# shield_v3.net
KiCad netlist of a schematic drawn in EAGLE
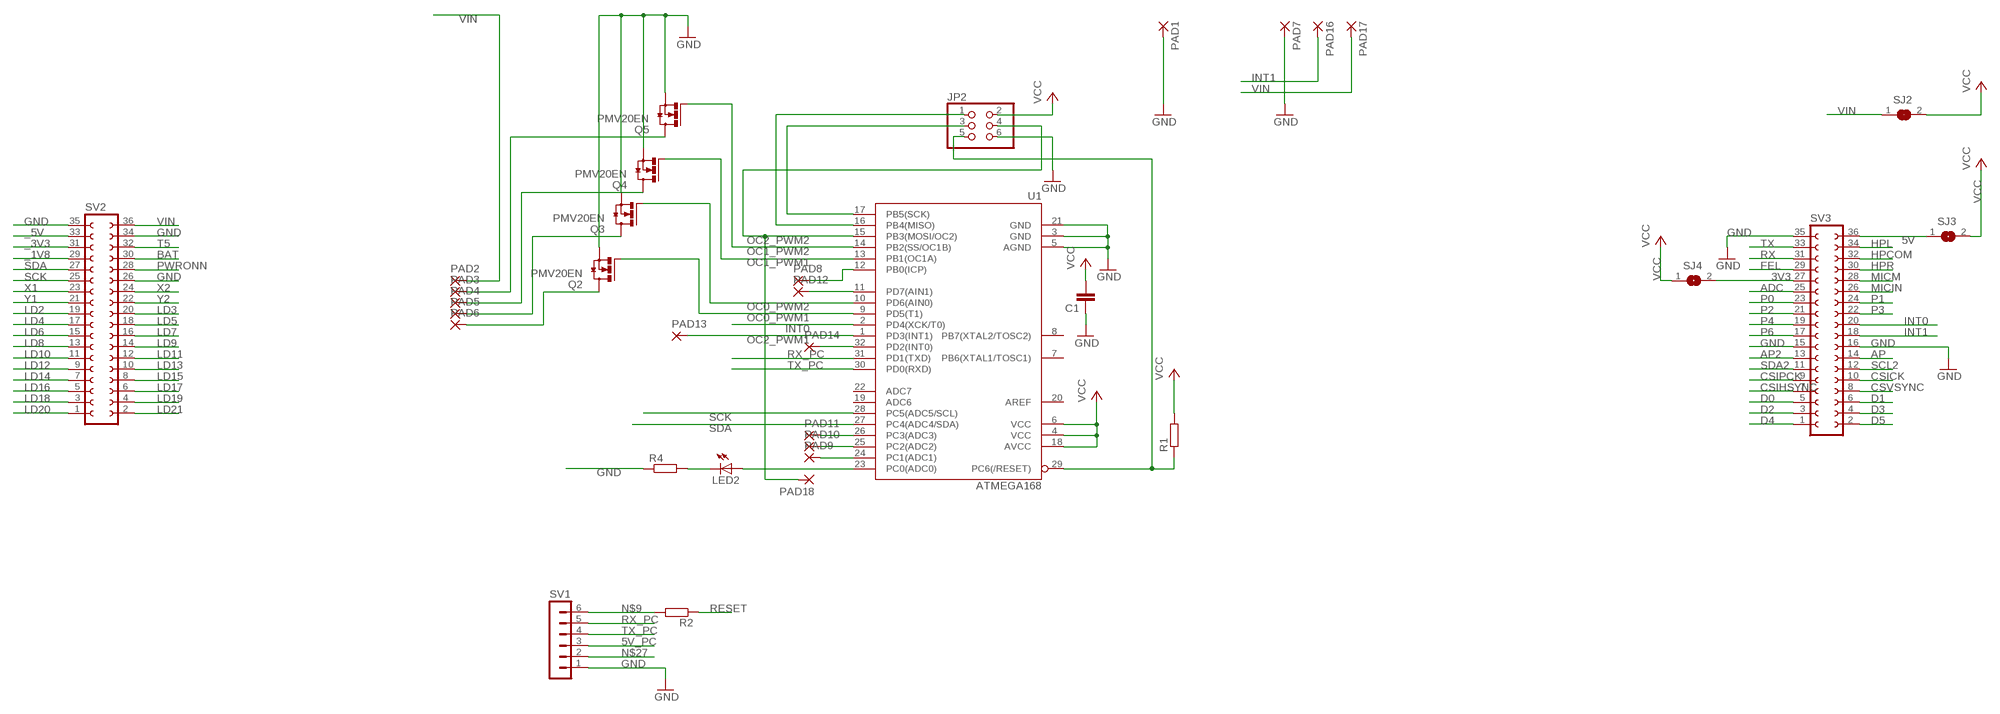
[diagram p0: schematic, sheet 1]

(export (version "E")
  (design (tool "Eeschema 10.0.6"))
  (components
    (comp (ref "C1")
      (value "C-EUC0805")
      (footprint "eagle-import:C0805")
      (libsource (lib "eagle-import") (part "C-EUC0805"))
    )
    (comp (ref "JP2")
      (value "PINHD-2X3")
      (footprint "eagle-import:2X03")
      (libsource (lib "eagle-import") (part "PINHD-2X3"))
    )
    (comp (ref "LED2")
      (value "LEDCHIP-LED0805")
      (footprint "eagle-import:CHIP-LED0805")
      (libsource (lib "eagle-import") (part "LEDCHIP-LED0805"))
    )
    (comp (ref "PAD1")
      (value "3,17/1,3")
      (footprint "eagle-import:3,17_1,3")
      (libsource (lib "eagle-import") (part "3,17/1,3"))
    )
    (comp (ref "PAD2")
      (value "3,17/1,3")
      (footprint "eagle-import:3,17_1,3")
      (libsource (lib "eagle-import") (part "3,17/1,3"))
    )
    (comp (ref "PAD3")
      (value "3,17/1,3")
      (footprint "eagle-import:3,17_1,3")
      (libsource (lib "eagle-import") (part "3,17/1,3"))
    )
    (comp (ref "PAD4")
      (value "3,17/1,3")
      (footprint "eagle-import:3,17_1,3")
      (libsource (lib "eagle-import") (part "3,17/1,3"))
    )
    (comp (ref "PAD5")
      (value "3,17/1,3")
      (footprint "eagle-import:3,17_1,3")
      (libsource (lib "eagle-import") (part "3,17/1,3"))
    )
    (comp (ref "PAD6")
      (value "3,17/1,3")
      (footprint "eagle-import:3,17_1,3")
      (libsource (lib "eagle-import") (part "3,17/1,3"))
    )
    (comp (ref "PAD7")
      (value "3,17/1,3")
      (footprint "eagle-import:3,17_1,3")
      (libsource (lib "eagle-import") (part "3,17/1,3"))
    )
    (comp (ref "PAD8")
      (value "SMD5")
      (footprint "eagle-import:SMD2,54-5,08")
      (libsource (lib "eagle-import") (part "SMD5"))
    )
    (comp (ref "PAD9")
      (value "3,17/1,3")
      (footprint "eagle-import:3,17_1,3")
      (libsource (lib "eagle-import") (part "3,17/1,3"))
    )
    (comp (ref "PAD10")
      (value "3,17/1,3")
      (footprint "eagle-import:3,17_1,3")
      (libsource (lib "eagle-import") (part "3,17/1,3"))
    )
    (comp (ref "PAD11")
      (value "3,17/1,3")
      (footprint "eagle-import:3,17_1,3")
      (libsource (lib "eagle-import") (part "3,17/1,3"))
    )
    (comp (ref "PAD12")
      (value "SMD5")
      (footprint "eagle-import:SMD2,54-5,08")
      (libsource (lib "eagle-import") (part "SMD5"))
    )
    (comp (ref "PAD13")
      (value "SMD2")
      (footprint "eagle-import:SMD1,27-2,54")
      (libsource (lib "eagle-import") (part "SMD2"))
    )
    (comp (ref "PAD14")
      (value "3,17/1,3")
      (footprint "eagle-import:3,17_1,3")
      (libsource (lib "eagle-import") (part "3,17/1,3"))
    )
    (comp (ref "PAD16")
      (value "3,17/1,3")
      (footprint "eagle-import:3,17_1,3")
      (libsource (lib "eagle-import") (part "3,17/1,3"))
    )
    (comp (ref "PAD17")
      (value "3,17/1,3")
      (footprint "eagle-import:3,17_1,3")
      (libsource (lib "eagle-import") (part "3,17/1,3"))
    )
    (comp (ref "PAD18")
      (value "3,17/1,3")
      (footprint "eagle-import:3,17_1,3")
      (libsource (lib "eagle-import") (part "3,17/1,3"))
    )
    (comp (ref "Q2")
      (value "PMV20EN")
      (footprint "eagle-import:SOT223")
      (libsource (lib "eagle-import") (part "NMOSFET_SMD_223"))
    )
    (comp (ref "Q3")
      (value "PMV20EN")
      (footprint "eagle-import:SOT223")
      (libsource (lib "eagle-import") (part "NMOSFET_SMD_223"))
    )
    (comp (ref "Q4")
      (value "PMV20EN")
      (footprint "eagle-import:SOT223")
      (libsource (lib "eagle-import") (part "NMOSFET_SMD_223"))
    )
    (comp (ref "Q5")
      (value "PMV20EN")
      (footprint "eagle-import:SOT223")
      (libsource (lib "eagle-import") (part "NMOSFET_SMD_223"))
    )
    (comp (ref "R1")
      (value "R-EU_M1206")
      (footprint "eagle-import:M1206")
      (libsource (lib "eagle-import") (part "R-EU_M1206"))
    )
    (comp (ref "R2")
      (value "R-EU_M1206")
      (footprint "eagle-import:M1206")
      (libsource (lib "eagle-import") (part "R-EU_M1206"))
    )
    (comp (ref "R4")
      (value "R-EU_M1206")
      (footprint "eagle-import:M1206")
      (libsource (lib "eagle-import") (part "R-EU_M1206"))
    )
    (comp (ref "SJ2") (value "SJ") (footprint "eagle-import:SJ") (libsource (lib "eagle-import") (part "SJ")))
    (comp (ref "SJ3") (value "SJ") (footprint "eagle-import:SJ") (libsource (lib "eagle-import") (part "SJ")))
    (comp (ref "SJ4") (value "SJ") (footprint "eagle-import:SJ") (libsource (lib "eagle-import") (part "SJ")))
    (comp (ref "SV1")
      (value "MA06-1")
      (footprint "eagle-import:MA06-1")
      (libsource (lib "eagle-import") (part "MA06-1"))
    )
    (comp (ref "SV2")
      (value "FE18-2")
      (footprint "eagle-import:FE18-2")
      (libsource (lib "eagle-import") (part "FE18-2"))
    )
    (comp (ref "SV3")
      (value "FE18-2")
      (footprint "eagle-import:FE18-2")
      (libsource (lib "eagle-import") (part "FE18-2"))
    )
    (comp (ref "U1")
      (value "ATMEGA168")
      (footprint "eagle-import:TQFP32-08")
      (libsource (lib "eagle-import") (part "ATMEGA168"))
    )
  )
  (nets
    (net (code "1") (name "/3V3") (class "Default")
      (node (ref "SJ4") (pin "2") (pinfunction "2_2") (pintype "passive"))
      (node (ref "SV3") (pin "27") (pinfunction "27_27") (pintype "passive"))
    )
    (net (code "2") (name "/5V") (class "Default")
      (node (ref "SJ3") (pin "1") (pinfunction "1_1") (pintype "passive"))
      (node (ref "SV3") (pin "36") (pinfunction "36_36") (pintype "passive"))
    )
    (net (code "3") (name "/5V_PC") (class "Default")
      (node (ref "SV1") (pin "3") (pinfunction "3_3") (pintype "passive"))
    )
    (net (code "4") (name "/ADC") (class "Default")
      (node (ref "SV3") (pin "25") (pinfunction "25_25") (pintype "passive"))
    )
    (net (code "5") (name "/AP") (class "Default")
      (node (ref "SV3") (pin "14") (pinfunction "14_14") (pintype "passive"))
    )
    (net (code "6") (name "/AP2") (class "Default")
      (node (ref "SV3") (pin "13") (pinfunction "13_13") (pintype "passive"))
    )
    (net (code "7") (name "/BAT") (class "Default")
      (node (ref "SV2") (pin "30") (pinfunction "30_30") (pintype "passive"))
    )
    (net (code "8") (name "/CSICK") (class "Default")
      (node (ref "SV3") (pin "10") (pinfunction "10_10") (pintype "passive"))
    )
    (net (code "9") (name "/CSIHSYNC") (class "Default")
      (node (ref "SV3") (pin "7") (pinfunction "7_7") (pintype "passive"))
    )
    (net (code "10") (name "/CSIPCK") (class "Default")
      (node (ref "SV3") (pin "9") (pinfunction "9_9") (pintype "passive"))
    )
    (net (code "11") (name "/CSVSYNC") (class "Default")
      (node (ref "SV3") (pin "8") (pinfunction "8_8") (pintype "passive"))
    )
    (net (code "12") (name "/D0") (class "Default")
      (node (ref "SV3") (pin "5") (pinfunction "5_5") (pintype "passive"))
    )
    (net (code "13") (name "/D1") (class "Default")
      (node (ref "SV3") (pin "6") (pinfunction "6_6") (pintype "passive"))
    )
    (net (code "14") (name "/D2") (class "Default")
      (node (ref "SV3") (pin "3") (pinfunction "3_3") (pintype "passive"))
    )
    (net (code "15") (name "/D3") (class "Default")
      (node (ref "SV3") (pin "4") (pinfunction "4_4") (pintype "passive"))
    )
    (net (code "16") (name "/D4") (class "Default")
      (node (ref "SV3") (pin "1") (pinfunction "1_1") (pintype "passive"))
    )
    (net (code "17") (name "/D5") (class "Default")
      (node (ref "SV3") (pin "2") (pinfunction "2_2") (pintype "passive"))
    )
    (net (code "18") (name "/FEL") (class "Default")
      (node (ref "SV3") (pin "29") (pinfunction "29_29") (pintype "passive"))
    )
    (net (code "19") (name "/HPCOM") (class "Default")
      (node (ref "SV3") (pin "32") (pinfunction "32_32") (pintype "passive"))
    )
    (net (code "20") (name "/HPL") (class "Default")
      (node (ref "SV3") (pin "34") (pinfunction "34_34") (pintype "passive"))
    )
    (net (code "21") (name "/HPR") (class "Default")
      (node (ref "SV3") (pin "30") (pinfunction "30_30") (pintype "passive"))
    )
    (net (code "22") (name "/INT0") (class "Default")
      (node (ref "SV3") (pin "20") (pinfunction "20_20") (pintype "passive"))
      (node (ref "U1") (pin "2") (pinfunction "PD4(XCK/T0)_2") (pintype "bidirectional"))
    )
    (net (code "23") (name "/INT1") (class "Default")
      (node (ref "PAD16") (pin "1") (pinfunction "P_1") (pintype "passive"))
      (node (ref "SV3") (pin "18") (pinfunction "18_18") (pintype "passive"))
    )
    (net (code "24") (name "/LD2") (class "Default")
      (node (ref "SV2") (pin "19") (pinfunction "19_19") (pintype "passive"))
    )
    (net (code "25") (name "/LD3") (class "Default")
      (node (ref "SV2") (pin "20") (pinfunction "20_20") (pintype "passive"))
    )
    (net (code "26") (name "/LD4") (class "Default")
      (node (ref "SV2") (pin "17") (pinfunction "17_17") (pintype "passive"))
    )
    (net (code "27") (name "/LD5") (class "Default")
      (node (ref "SV2") (pin "18") (pinfunction "18_18") (pintype "passive"))
    )
    (net (code "28") (name "/LD6") (class "Default")
      (node (ref "SV2") (pin "15") (pinfunction "15_15") (pintype "passive"))
    )
    (net (code "29") (name "/LD7") (class "Default")
      (node (ref "SV2") (pin "16") (pinfunction "16_16") (pintype "passive"))
    )
    (net (code "30") (name "/LD8") (class "Default")
      (node (ref "SV2") (pin "13") (pinfunction "13_13") (pintype "passive"))
    )
    (net (code "31") (name "/LD9") (class "Default")
      (node (ref "SV2") (pin "14") (pinfunction "14_14") (pintype "passive"))
    )
    (net (code "32") (name "/LD10") (class "Default")
      (node (ref "SV2") (pin "11") (pinfunction "11_11") (pintype "passive"))
    )
    (net (code "33") (name "/LD11") (class "Default")
      (node (ref "SV2") (pin "12") (pinfunction "12_12") (pintype "passive"))
    )
    (net (code "34") (name "/LD12") (class "Default")
      (node (ref "SV2") (pin "9") (pinfunction "9_9") (pintype "passive"))
    )
    (net (code "35") (name "/LD13") (class "Default")
      (node (ref "SV2") (pin "10") (pinfunction "10_10") (pintype "passive"))
    )
    (net (code "36") (name "/LD14") (class "Default")
      (node (ref "SV2") (pin "7") (pinfunction "7_7") (pintype "passive"))
    )
    (net (code "37") (name "/LD15") (class "Default")
      (node (ref "SV2") (pin "8") (pinfunction "8_8") (pintype "passive"))
    )
    (net (code "38") (name "/LD16") (class "Default")
      (node (ref "SV2") (pin "5") (pinfunction "5_5") (pintype "passive"))
    )
    (net (code "39") (name "/LD17") (class "Default")
      (node (ref "SV2") (pin "6") (pinfunction "6_6") (pintype "passive"))
    )
    (net (code "40") (name "/LD18") (class "Default")
      (node (ref "SV2") (pin "3") (pinfunction "3_3") (pintype "passive"))
    )
    (net (code "41") (name "/LD19") (class "Default")
      (node (ref "SV2") (pin "4") (pinfunction "4_4") (pintype "passive"))
    )
    (net (code "42") (name "/LD20") (class "Default")
      (node (ref "SV2") (pin "1") (pinfunction "1_1") (pintype "passive"))
    )
    (net (code "43") (name "/LD21") (class "Default")
      (node (ref "SV2") (pin "2") (pinfunction "2_2") (pintype "passive"))
    )
    (net (code "44") (name "/MICIN") (class "Default")
      (node (ref "SV3") (pin "26") (pinfunction "26_26") (pintype "passive"))
    )
    (net (code "45") (name "/MICM") (class "Default")
      (node (ref "SV3") (pin "28") (pinfunction "28_28") (pintype "passive"))
    )
    (net (code "46") (name "/N$9") (class "Default")
      (node (ref "R2") (pin "2") (pinfunction "2_2") (pintype "passive"))
      (node (ref "SV1") (pin "6") (pinfunction "6_6") (pintype "passive"))
    )
    (net (code "47") (name "/N$27") (class "Default")
      (node (ref "SV1") (pin "2") (pinfunction "2_2") (pintype "passive"))
    )
    (net (code "48") (name "/OC0_PWM1") (class "Default")
      (node (ref "Q2") (pin "1") (pinfunction "G_1") (pintype "passive"))
      (node (ref "U1") (pin "9") (pinfunction "PD5(T1)_9") (pintype "bidirectional"))
    )
    (net (code "49") (name "/OC0_PWM2") (class "Default")
      (node (ref "Q3") (pin "1") (pinfunction "G_1") (pintype "passive"))
      (node (ref "U1") (pin "10") (pinfunction "PD6(AIN0)_10") (pintype "bidirectional"))
    )
    (net (code "50") (name "/OC1_PWM1") (class "Default")
      (node (ref "Q4") (pin "1") (pinfunction "G_1") (pintype "passive"))
      (node (ref "U1") (pin "13") (pinfunction "PB1(OC1A)_13") (pintype "bidirectional"))
    )
    (net (code "51") (name "/OC1_PWM2") (class "Default")
      (node (ref "Q5") (pin "1") (pinfunction "G_1") (pintype "passive"))
      (node (ref "U1") (pin "14") (pinfunction "PB2(SS/OC1B)_14") (pintype "bidirectional"))
    )
    (net (code "52") (name "/OC2_PWM1") (class "Default")
      (node (ref "PAD13") (pin "1") (pinfunction "P_1") (pintype "passive"))
      (node (ref "U1") (pin "1") (pinfunction "PD3(INT1)_1") (pintype "bidirectional"))
    )
    (net (code "53") (name "/OC2_PWM2") (class "Default")
      (node (ref "JP2") (pin "4") (pinfunction "4_4") (pintype "passive"))
      (node (ref "PAD18") (pin "1") (pinfunction "P_1") (pintype "passive"))
      (node (ref "U1") (pin "15") (pinfunction "PB3(MOSI/OC2)_15") (pintype "bidirectional"))
    )
    (net (code "54") (name "/P0") (class "Default")
      (node (ref "SV3") (pin "23") (pinfunction "23_23") (pintype "passive"))
    )
    (net (code "55") (name "/P1") (class "Default")
      (node (ref "SV3") (pin "24") (pinfunction "24_24") (pintype "passive"))
    )
    (net (code "56") (name "/P2") (class "Default")
      (node (ref "SV3") (pin "21") (pinfunction "21_21") (pintype "passive"))
    )
    (net (code "57") (name "/P3") (class "Default")
      (node (ref "SV3") (pin "22") (pinfunction "22_22") (pintype "passive"))
    )
    (net (code "58") (name "/P4") (class "Default")
      (node (ref "SV3") (pin "19") (pinfunction "19_19") (pintype "passive"))
    )
    (net (code "59") (name "/P6") (class "Default")
      (node (ref "SV3") (pin "17") (pinfunction "17_17") (pintype "passive"))
    )
    (net (code "60") (name "/PWRONN") (class "Default")
      (node (ref "SV2") (pin "28") (pinfunction "28_28") (pintype "passive"))
    )
    (net (code "61") (name "/RESET") (class "Default")
      (node (ref "JP2") (pin "5") (pinfunction "5_5") (pintype "passive"))
      (node (ref "R1") (pin "1") (pinfunction "1_1") (pintype "passive"))
      (node (ref "R2") (pin "1") (pinfunction "1_1") (pintype "passive"))
      (node (ref "U1") (pin "29") (pinfunction "PC6(/RESET)_29") (pintype "bidirectional"))
    )
    (net (code "62") (name "/RX") (class "Default")
      (node (ref "SV3") (pin "31") (pinfunction "31_31") (pintype "passive"))
    )
    (net (code "63") (name "/RX_PC") (class "Default")
      (node (ref "SV1") (pin "5") (pinfunction "5_5") (pintype "passive"))
      (node (ref "U1") (pin "31") (pinfunction "PD1(TXD)_31") (pintype "bidirectional"))
    )
    (net (code "64") (name "/SCK") (class "Default")
      (node (ref "SV2") (pin "25") (pinfunction "25_25") (pintype "passive"))
      (node (ref "U1") (pin "28") (pinfunction "PC5(ADC5/SCL)_28") (pintype "bidirectional"))
    )
    (net (code "65") (name "/SCL2") (class "Default")
      (node (ref "SV3") (pin "12") (pinfunction "12_12") (pintype "passive"))
    )
    (net (code "66") (name "/SDA") (class "Default")
      (node (ref "SV2") (pin "27") (pinfunction "27_27") (pintype "passive"))
      (node (ref "U1") (pin "27") (pinfunction "PC4(ADC4/SDA)_27") (pintype "bidirectional"))
    )
    (net (code "67") (name "/SDA2") (class "Default")
      (node (ref "SV3") (pin "11") (pinfunction "11_11") (pintype "passive"))
    )
    (net (code "68") (name "/T5") (class "Default")
      (node (ref "SV2") (pin "32") (pinfunction "32_32") (pintype "passive"))
    )
    (net (code "69") (name "/TX") (class "Default")
      (node (ref "SV3") (pin "33") (pinfunction "33_33") (pintype "passive"))
    )
    (net (code "70") (name "/TX_PC") (class "Default")
      (node (ref "SV1") (pin "4") (pinfunction "4_4") (pintype "passive"))
      (node (ref "U1") (pin "30") (pinfunction "PD0(RXD)_30") (pintype "bidirectional"))
    )
    (net (code "71") (name "/VIN") (class "Default")
      (node (ref "PAD17") (pin "1") (pinfunction "P_1") (pintype "passive"))
      (node (ref "PAD2") (pin "1") (pinfunction "P_1") (pintype "passive"))
      (node (ref "SJ2") (pin "1") (pinfunction "1_1") (pintype "passive"))
      (node (ref "SV2") (pin "36") (pinfunction "36_36") (pintype "passive"))
    )
    (net (code "72") (name "/X1") (class "Default")
      (node (ref "SV2") (pin "23") (pinfunction "23_23") (pintype "passive"))
    )
    (net (code "73") (name "/X2") (class "Default")
      (node (ref "SV2") (pin "24") (pinfunction "24_24") (pintype "passive"))
    )
    (net (code "74") (name "/Y1") (class "Default")
      (node (ref "SV2") (pin "21") (pinfunction "21_21") (pintype "passive"))
    )
    (net (code "75") (name "/Y2") (class "Default")
      (node (ref "SV2") (pin "22") (pinfunction "22_22") (pintype "passive"))
    )
    (net (code "76") (name "/_1V8") (class "Default")
      (node (ref "SV2") (pin "29") (pinfunction "29_29") (pintype "passive"))
    )
    (net (code "77") (name "/_3V3") (class "Default")
      (node (ref "SV2") (pin "31") (pinfunction "31_31") (pintype "passive"))
    )
    (net (code "78") (name "/_5V") (class "Default")
      (node (ref "SV2") (pin "33") (pinfunction "33_33") (pintype "passive"))
    )
    (net (code "79") (name "GND") (class "Default")
      (node (ref "C1") (pin "1") (pinfunction "1_1") (pintype "passive"))
      (node (ref "JP2") (pin "6") (pinfunction "6_6") (pintype "passive"))
      (node (ref "PAD1") (pin "1") (pinfunction "P_1") (pintype "passive"))
      (node (ref "PAD7") (pin "1") (pinfunction "P_1") (pintype "passive"))
      (node (ref "Q2") (pin "3") (pinfunction "S_3") (pintype "passive"))
      (node (ref "Q3") (pin "3") (pinfunction "S_3") (pintype "passive"))
      (node (ref "Q4") (pin "3") (pinfunction "S_3") (pintype "passive"))
      (node (ref "Q5") (pin "3") (pinfunction "S_3") (pintype "passive"))
      (node (ref "R4") (pin "1") (pinfunction "1_1") (pintype "passive"))
      (node (ref "SV1") (pin "1") (pinfunction "1_1") (pintype "passive"))
      (node (ref "SV2") (pin "26") (pinfunction "26_26") (pintype "passive"))
      (node (ref "SV2") (pin "34") (pinfunction "34_34") (pintype "passive"))
      (node (ref "SV2") (pin "35") (pinfunction "35_35") (pintype "passive"))
      (node (ref "SV3") (pin "15") (pinfunction "15_15") (pintype "passive"))
      (node (ref "SV3") (pin "16") (pinfunction "16_16") (pintype "passive"))
      (node (ref "SV3") (pin "35") (pinfunction "35_35") (pintype "passive"))
      (node (ref "U1") (pin "21") (pinfunction "GND_21") (pintype "bidirectional"))
      (node (ref "U1") (pin "3") (pinfunction "GND_3") (pintype "bidirectional"))
      (node (ref "U1") (pin "5") (pinfunction "AGND_5") (pintype "bidirectional"))
    )
    (net (code "80") (name "Net-(LED2-PadC)") (class "Default")
      (node (ref "LED2") (pin "C") (pinfunction "C_C") (pintype "passive"))
      (node (ref "R4") (pin "2") (pinfunction "2_2") (pintype "passive"))
    )
    (net (code "81") (name "Net-(PAD3-P)") (class "Default")
      (node (ref "PAD3") (pin "1") (pinfunction "P_1") (pintype "passive"))
      (node (ref "Q5") (pin "2") (pinfunction "D_2") (pintype "passive"))
      (node (ref "Q5") (pin "4") (pinfunction "D_4") (pintype "passive"))
    )
    (net (code "82") (name "Net-(PAD4-P)") (class "Default")
      (node (ref "PAD4") (pin "1") (pinfunction "P_1") (pintype "passive"))
      (node (ref "Q4") (pin "2") (pinfunction "D_2") (pintype "passive"))
      (node (ref "Q4") (pin "4") (pinfunction "D_4") (pintype "passive"))
    )
    (net (code "83") (name "Net-(PAD5-P)") (class "Default")
      (node (ref "PAD5") (pin "1") (pinfunction "P_1") (pintype "passive"))
      (node (ref "Q3") (pin "2") (pinfunction "D_2") (pintype "passive"))
      (node (ref "Q3") (pin "4") (pinfunction "D_4") (pintype "passive"))
    )
    (net (code "84") (name "Net-(PAD6-P)") (class "Default")
      (node (ref "PAD6") (pin "1") (pinfunction "P_1") (pintype "passive"))
      (node (ref "Q2") (pin "2") (pinfunction "D_2") (pintype "passive"))
      (node (ref "Q2") (pin "4") (pinfunction "D_4") (pintype "passive"))
    )
    (net (code "85") (name "Net-(PAD8-P)") (class "Default")
      (node (ref "PAD8") (pin "1") (pinfunction "P_1") (pintype "passive"))
      (node (ref "U1") (pin "12") (pinfunction "PB0(ICP)_12") (pintype "bidirectional"))
    )
    (net (code "86") (name "Net-(PAD9-P)") (class "Default")
      (node (ref "PAD9") (pin "1") (pinfunction "P_1") (pintype "passive"))
      (node (ref "U1") (pin "24") (pinfunction "PC1(ADC1)_24") (pintype "bidirectional"))
    )
    (net (code "87") (name "Net-(PAD10-P)") (class "Default")
      (node (ref "PAD10") (pin "1") (pinfunction "P_1") (pintype "passive"))
      (node (ref "U1") (pin "25") (pinfunction "PC2(ADC2)_25") (pintype "bidirectional"))
    )
    (net (code "88") (name "Net-(PAD11-P)") (class "Default")
      (node (ref "PAD11") (pin "1") (pinfunction "P_1") (pintype "passive"))
      (node (ref "U1") (pin "26") (pinfunction "PC3(ADC3)_26") (pintype "bidirectional"))
    )
    (net (code "89") (name "Net-(PAD12-P)") (class "Default")
      (node (ref "PAD12") (pin "1") (pinfunction "P_1") (pintype "passive"))
      (node (ref "U1") (pin "11") (pinfunction "PD7(AIN1)_11") (pintype "bidirectional"))
    )
    (net (code "90") (name "Net-(PAD14-P)") (class "Default")
      (node (ref "PAD14") (pin "1") (pinfunction "P_1") (pintype "passive"))
      (node (ref "U1") (pin "32") (pinfunction "PD2(INT0)_32") (pintype "bidirectional"))
    )
    (net (code "91") (name "Net-(U1-PB4(MISO))") (class "Default")
      (node (ref "JP2") (pin "1") (pinfunction "1_1") (pintype "passive"))
      (node (ref "U1") (pin "16") (pinfunction "PB4(MISO)_16") (pintype "bidirectional"))
    )
    (net (code "92") (name "Net-(U1-PB5(SCK))") (class "Default")
      (node (ref "JP2") (pin "3") (pinfunction "3_3") (pintype "passive"))
      (node (ref "U1") (pin "17") (pinfunction "PB5(SCK)_17") (pintype "bidirectional"))
    )
    (net (code "93") (name "Net-(U1-PC0(ADC0))") (class "Default")
      (node (ref "LED2") (pin "A") (pinfunction "A_A") (pintype "passive"))
      (node (ref "U1") (pin "23") (pinfunction "PC0(ADC0)_23") (pintype "bidirectional"))
    )
    (net (code "94") (name "VCC") (class "Default")
      (node (ref "C1") (pin "2") (pinfunction "2_2") (pintype "passive"))
      (node (ref "JP2") (pin "2") (pinfunction "2_2") (pintype "passive"))
      (node (ref "R1") (pin "2") (pinfunction "2_2") (pintype "passive"))
      (node (ref "SJ2") (pin "2") (pinfunction "2_2") (pintype "passive"))
      (node (ref "SJ3") (pin "2") (pinfunction "2_2") (pintype "passive"))
      (node (ref "SJ4") (pin "1") (pinfunction "1_1") (pintype "passive"))
      (node (ref "U1") (pin "18") (pinfunction "AVCC_18") (pintype "bidirectional"))
      (node (ref "U1") (pin "4") (pinfunction "VCC_4") (pintype "bidirectional"))
      (node (ref "U1") (pin "6") (pinfunction "VCC_6") (pintype "bidirectional"))
    )
    (net (code "95") (name "unconnected-(U1-ADC6-Pad19)") (class "Default")
      (node (ref "U1") (pin "19") (pinfunction "ADC6_19") (pintype "bidirectional"))
    )
    (net (code "96") (name "unconnected-(U1-ADC7-Pad22)") (class "Default")
      (node (ref "U1") (pin "22") (pinfunction "ADC7_22") (pintype "bidirectional"))
    )
    (net (code "97") (name "unconnected-(U1-AREF-Pad20)") (class "Default")
      (node (ref "U1") (pin "20") (pinfunction "AREF_20") (pintype "bidirectional"))
    )
    (net (code "98") (name "unconnected-(U1-PB6(XTAL1{slash}TOSC1)-Pad7)") (class "Default")
      (node (ref "U1") (pin "7") (pinfunction "PB6(XTAL1/TOSC1)_7") (pintype "bidirectional"))
    )
    (net (code "99") (name "unconnected-(U1-PB7(XTAL2{slash}TOSC2)-Pad8)") (class "Default")
      (node (ref "U1") (pin "8") (pinfunction "PB7(XTAL2/TOSC2)_8") (pintype "bidirectional"))
    )
  )
)
